# ATtinyNode.net
KiCad netlist of a schematic drawn in EAGLE
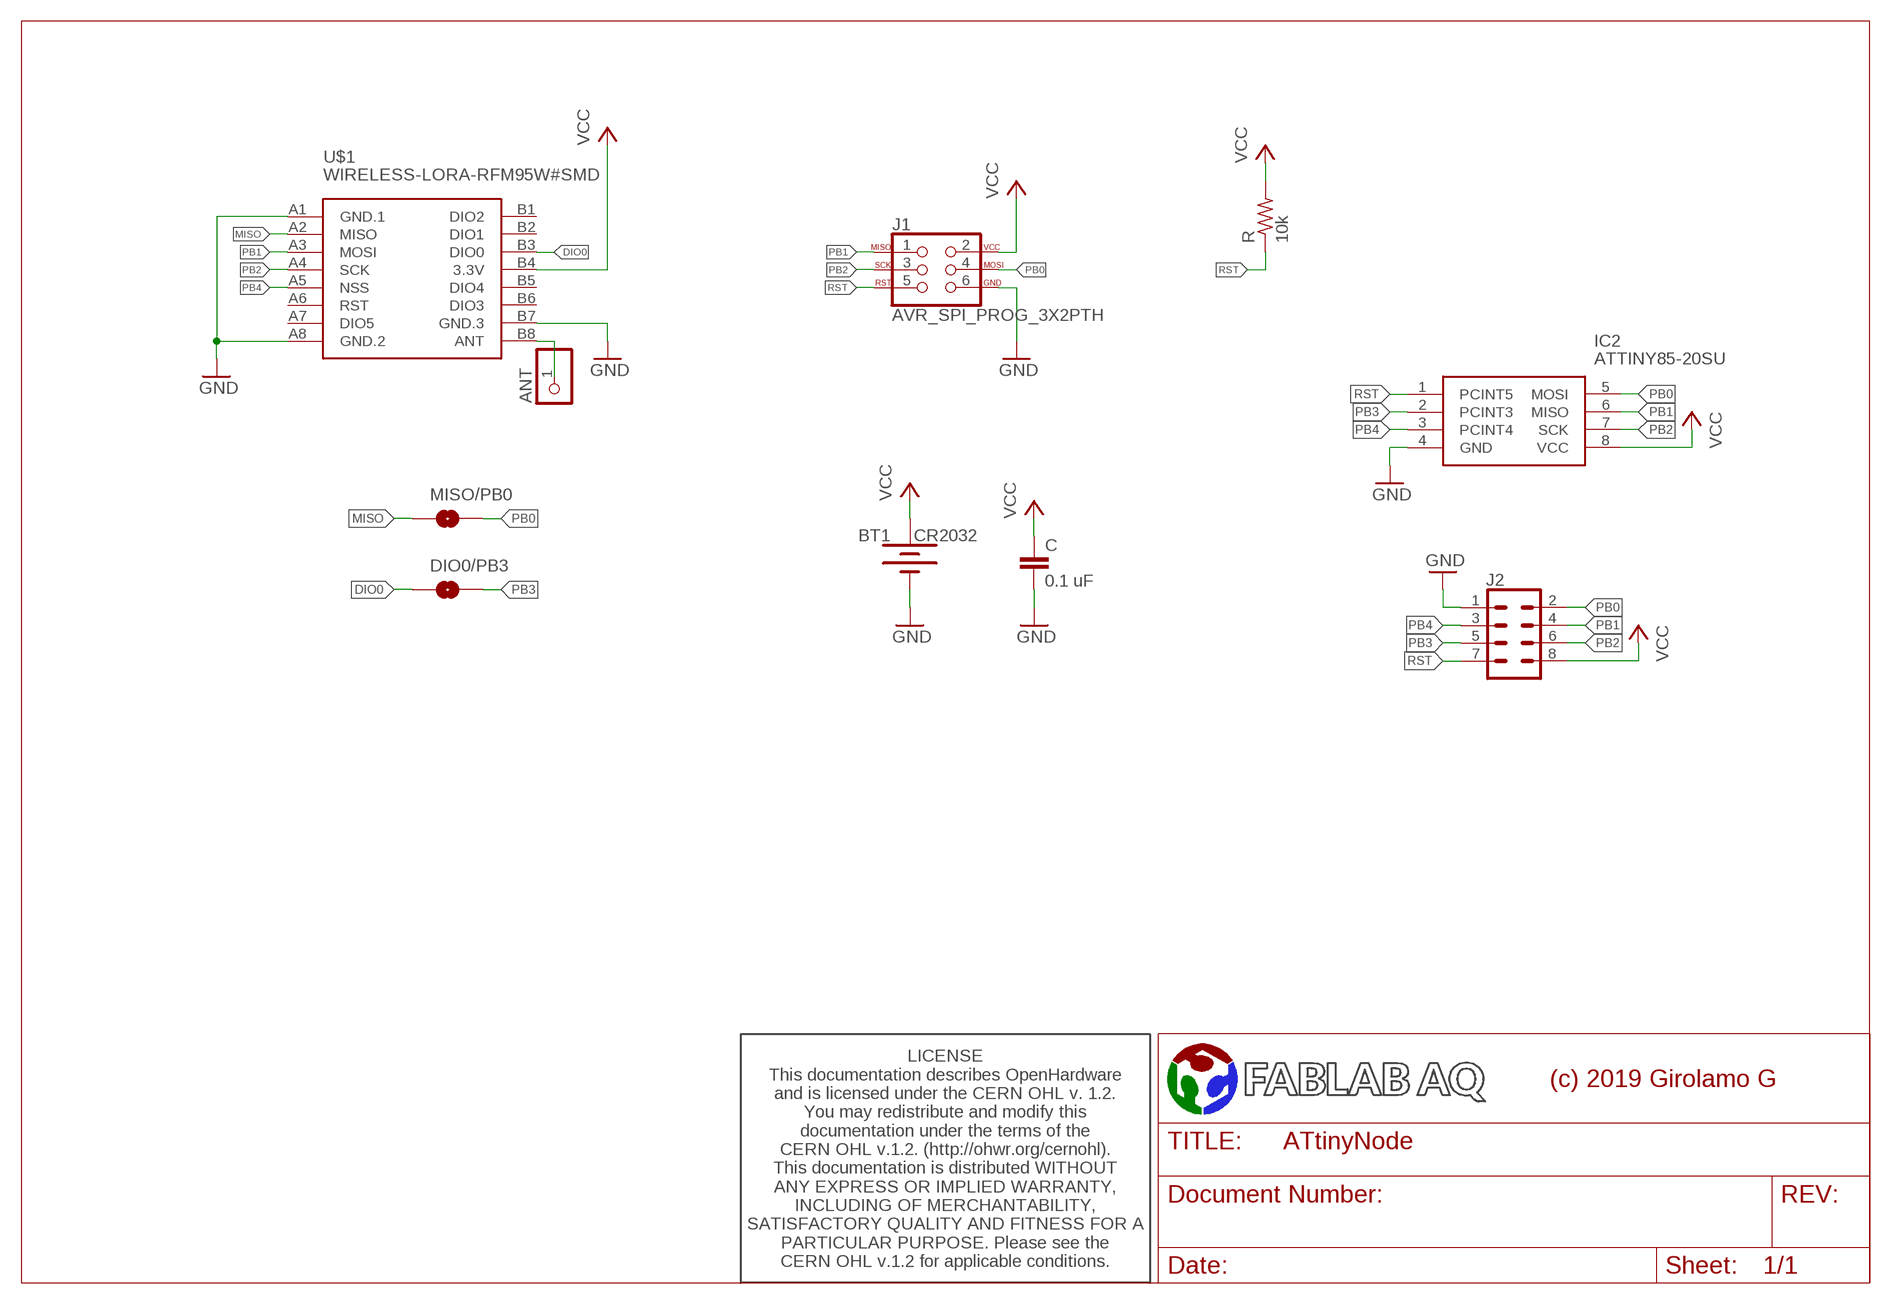
[diagram p0: schematic, sheet 1]

(export (version "E")
  (design (tool "Eeschema 10.0.6"))
  (components
    (comp (ref "ANT")
      (value "PINHD-1X1CB")
      (footprint "eagle-import:1X01-CLEANBIG")
      (libsource (lib "eagle-import") (part "PINHD-1X1CB"))
    )
    (comp (ref "BT1")
      (value "CR2032")
      (footprint "eagle-import:BATTCOM_20MM_PTH")
      (libsource (lib "eagle-import") (part "BATTERY-20MM_PTH"))
    )
    (comp (ref "C")
      (value "0.1 uF")
      (footprint "eagle-import:C0805")
      (libsource (lib "eagle-import") (part "C-EUC0805"))
    )
    (comp (ref "DIO0/PB3")
      (value "JUMPER-SMT_2_NO_SILK")
      (footprint "eagle-import:SMT-JUMPER_2_NO_SILK")
      (libsource (lib "eagle-import") (part "JUMPER-SMT_2_NO_SILK"))
    )
    (comp (ref "IC2")
      (value "ATTINY85-20SU")
      (footprint "eagle-import:SOT127P798X216-8N")
      (fields
        (field (name "MOUSER_PART_NUMBER") "556-ATTINY85-20SU")
        (field (name "RS_PART_NUMBER") "1331674")
      )
      (libsource (lib "eagle-import") (part "ATTINY85-20SU"))
    )
    (comp (ref "J1")
      (value "AVR_SPI_PROG_3X2PTH")
      (footprint "eagle-import:2X3")
      (libsource (lib "eagle-import") (part "AVR_SPI_PROG_3X2PTH"))
    )
    (comp (ref "J2")
      (value "CONN_04X2")
      (footprint "eagle-import:2X4")
      (libsource (lib "eagle-import") (part "CONN_04X2"))
    )
    (comp (ref "MISO/PB0")
      (value "JUMPER-SMT_2_NO_SILK")
      (footprint "eagle-import:SMT-JUMPER_2_NO_SILK")
      (libsource (lib "eagle-import") (part "JUMPER-SMT_2_NO_SILK"))
    )
    (comp (ref "R")
      (value "10k")
      (footprint "eagle-import:R0805")
      (libsource (lib "eagle-import") (part "R-US_R0805"))
    )
    (comp (ref "U$1")
      (value "WIRELESS-LORA-RFM95W#SMD")
      (footprint "eagle-import:WIRELESS-LORA-RFM95W#SMD")
      (libsource (lib "eagle-import") (part "WIRELESS-LORA-RFM95W#SMD"))
    )
    (comp (ref "U$2")
      (value "FABLABAQ_LOGONONE")
      (footprint "eagle-import:NONE")
      (libsource (lib "eagle-import") (part "FABLABAQ_LOGONONE"))
    )
    (comp (ref "U$3")
      (value "CERN_OHL_1.2")
      (footprint "eagle-import:DOC_CERN_OHL_1.2")
      (libsource (lib "eagle-import") (part "CERN_OHL_1.2"))
    )
  )
  (nets
    (net (code "1") (name "DIO0") (class "Default")
      (node (ref "DIO0/PB3") (pin "1") (pinfunction "1_1") (pintype "passive"))
      (node (ref "U$1") (pin "B3") (pinfunction "DIO0_B3") (pintype "bidirectional"))
    )
    (net (code "2") (name "GND") (class "Default")
      (node (ref "BT1") (pin "2") (pinfunction "-_2") (pintype "power_in"))
      (node (ref "C") (pin "2") (pinfunction "2_2") (pintype "passive"))
      (node (ref "IC2") (pin "4") (pinfunction "GND_4") (pintype "power_in"))
      (node (ref "J1") (pin "6") (pinfunction "6_6") (pintype "passive"))
      (node (ref "J2") (pin "1") (pinfunction "1_1") (pintype "passive"))
      (node (ref "U$1") (pin "A1") (pinfunction "GND.1_A1") (pintype "power_in"))
      (node (ref "U$1") (pin "A8") (pinfunction "GND.2_A8") (pintype "power_in"))
      (node (ref "U$1") (pin "B7") (pinfunction "GND.3_B7") (pintype "power_in"))
    )
    (net (code "3") (name "MISO") (class "Default")
      (node (ref "MISO/PB0") (pin "1") (pinfunction "1_1") (pintype "passive"))
      (node (ref "U$1") (pin "A2") (pinfunction "MISO_A2") (pintype "bidirectional"))
    )
    (net (code "4") (name "Net-(U$1-ANT)") (class "Default")
      (node (ref "ANT") (pin "1") (pinfunction "1_1") (pintype "passive"))
      (node (ref "U$1") (pin "B8") (pinfunction "ANT_B8") (pintype "passive"))
    )
    (net (code "5") (name "PB0") (class "Default")
      (node (ref "IC2") (pin "5") (pinfunction "MOSI_5") (pintype "bidirectional"))
      (node (ref "J1") (pin "4") (pinfunction "4_4") (pintype "passive"))
      (node (ref "J2") (pin "2") (pinfunction "2_2") (pintype "passive"))
      (node (ref "MISO/PB0") (pin "2") (pinfunction "2_2") (pintype "passive"))
    )
    (net (code "6") (name "PB1") (class "Default")
      (node (ref "IC2") (pin "6") (pinfunction "MISO_6") (pintype "bidirectional"))
      (node (ref "J1") (pin "1") (pinfunction "1_1") (pintype "passive"))
      (node (ref "J2") (pin "4") (pinfunction "4_4") (pintype "passive"))
      (node (ref "U$1") (pin "A3") (pinfunction "MOSI_A3") (pintype "bidirectional"))
    )
    (net (code "7") (name "PB2") (class "Default")
      (node (ref "IC2") (pin "7") (pinfunction "SCK_7") (pintype "bidirectional"))
      (node (ref "J1") (pin "3") (pinfunction "3_3") (pintype "passive"))
      (node (ref "J2") (pin "6") (pinfunction "6_6") (pintype "passive"))
      (node (ref "U$1") (pin "A4") (pinfunction "SCK_A4") (pintype "bidirectional"))
    )
    (net (code "8") (name "PB3") (class "Default")
      (node (ref "DIO0/PB3") (pin "2") (pinfunction "2_2") (pintype "passive"))
      (node (ref "IC2") (pin "2") (pinfunction "PCINT3_2") (pintype "bidirectional"))
      (node (ref "J2") (pin "5") (pinfunction "5_5") (pintype "passive"))
    )
    (net (code "9") (name "PB4") (class "Default")
      (node (ref "IC2") (pin "3") (pinfunction "PCINT4_3") (pintype "bidirectional"))
      (node (ref "J2") (pin "3") (pinfunction "3_3") (pintype "passive"))
      (node (ref "U$1") (pin "A5") (pinfunction "NSS_A5") (pintype "bidirectional"))
    )
    (net (code "10") (name "RST") (class "Default")
      (node (ref "IC2") (pin "1") (pinfunction "PCINT5_1") (pintype "bidirectional"))
      (node (ref "J1") (pin "5") (pinfunction "5_5") (pintype "passive"))
      (node (ref "J2") (pin "7") (pinfunction "7_7") (pintype "passive"))
      (node (ref "R") (pin "1") (pinfunction "1_1") (pintype "passive"))
    )
    (net (code "11") (name "VCC") (class "Default")
      (node (ref "BT1") (pin "1") (pinfunction "+_1") (pintype "power_in"))
      (node (ref "C") (pin "1") (pinfunction "1_1") (pintype "passive"))
      (node (ref "IC2") (pin "8") (pinfunction "VCC_8") (pintype "power_in"))
      (node (ref "J1") (pin "2") (pinfunction "2_2") (pintype "passive"))
      (node (ref "J2") (pin "8") (pinfunction "8_8") (pintype "passive"))
      (node (ref "R") (pin "2") (pinfunction "2_2") (pintype "passive"))
      (node (ref "U$1") (pin "B4") (pinfunction "3.3V_B4") (pintype "power_in"))
    )
    (net (code "12") (name "unconnected-(U$1-DIO1-PadB2)") (class "Default")
      (node (ref "U$1") (pin "B2") (pinfunction "DIO1_B2") (pintype "bidirectional"))
    )
    (net (code "13") (name "unconnected-(U$1-DIO2-PadB1)") (class "Default")
      (node (ref "U$1") (pin "B1") (pinfunction "DIO2_B1") (pintype "bidirectional"))
    )
    (net (code "14") (name "unconnected-(U$1-DIO3-PadB6)") (class "Default")
      (node (ref "U$1") (pin "B6") (pinfunction "DIO3_B6") (pintype "bidirectional"))
    )
    (net (code "15") (name "unconnected-(U$1-DIO4-PadB5)") (class "Default")
      (node (ref "U$1") (pin "B5") (pinfunction "DIO4_B5") (pintype "bidirectional"))
    )
    (net (code "16") (name "unconnected-(U$1-DIO5-PadA7)") (class "Default")
      (node (ref "U$1") (pin "A7") (pinfunction "DIO5_A7") (pintype "bidirectional"))
    )
    (net (code "17") (name "unconnected-(U$1-RST-PadA6)") (class "Default")
      (node (ref "U$1") (pin "A6") (pinfunction "RST_A6") (pintype "bidirectional"))
    )
  )
)
